# NyanTimer-v7.net
KiCad netlist of a schematic drawn in EAGLE
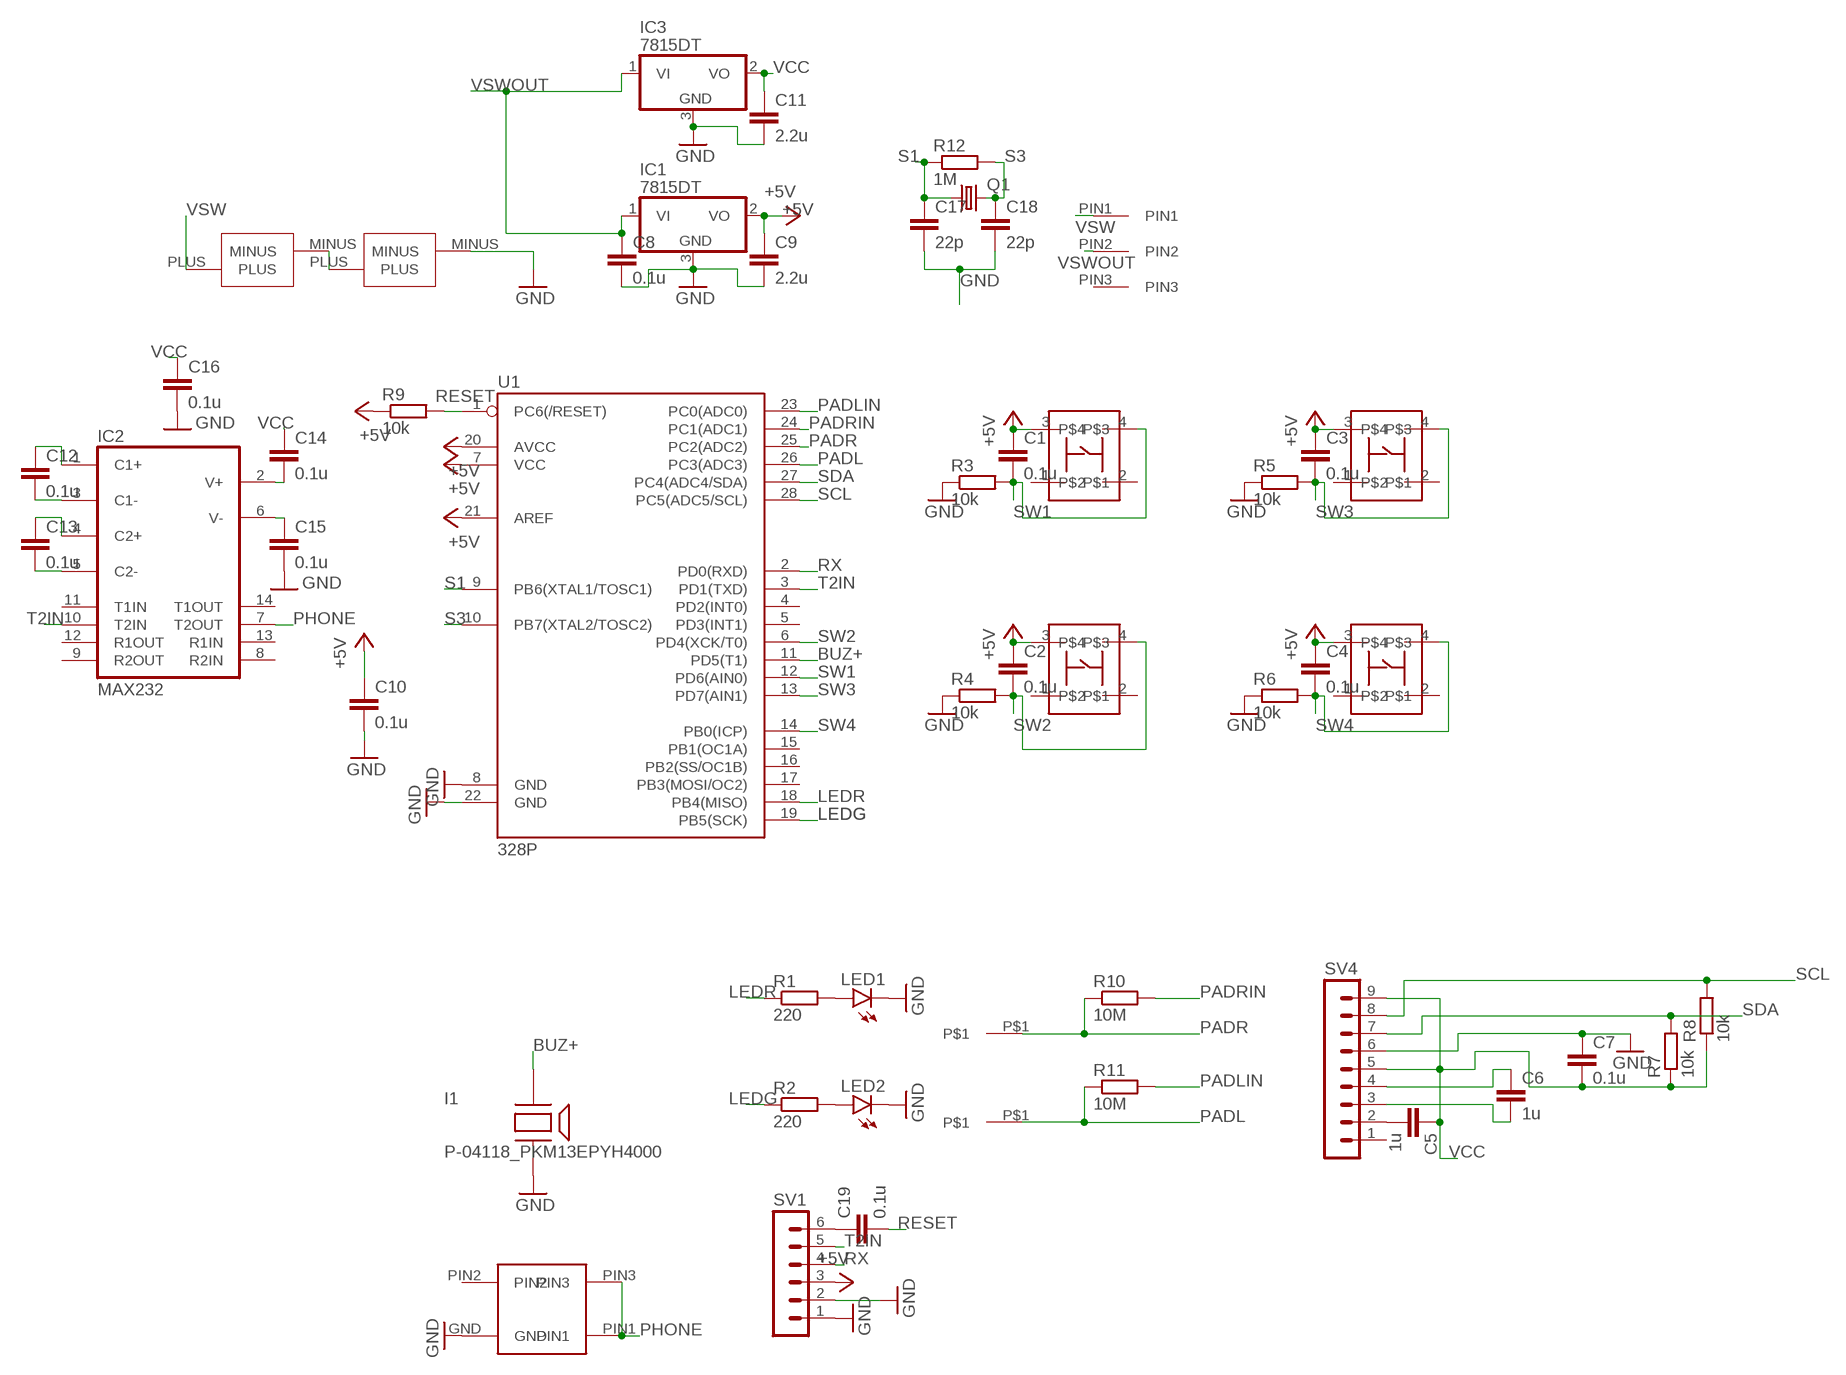
[diagram p0: schematic, sheet 1]

(export (version "E")
  (design (tool "Eeschema 10.0.6"))
  (components
    (comp (ref "BT1")
      (value "AKIZUKI_CR2032")
      (footprint "eagle-import:AKIZUKI_CR2032")
      (libsource (lib "eagle-import") (part "AKIZUKI_CR2032"))
    )
    (comp (ref "BT2")
      (value "AKIZUKI_CR2032")
      (footprint "eagle-import:AKIZUKI_CR2032")
      (libsource (lib "eagle-import") (part "AKIZUKI_CR2032"))
    )
    (comp (ref "C1")
      (value "0.1u")
      (footprint "eagle-import:C025-024X044")
      (libsource (lib "eagle-import") (part "C-EU025-024X044"))
    )
    (comp (ref "C2")
      (value "0.1u")
      (footprint "eagle-import:C025-024X044")
      (libsource (lib "eagle-import") (part "C-EU025-024X044"))
    )
    (comp (ref "C3")
      (value "0.1u")
      (footprint "eagle-import:C025-024X044")
      (libsource (lib "eagle-import") (part "C-EU025-024X044"))
    )
    (comp (ref "C4")
      (value "0.1u")
      (footprint "eagle-import:C025-024X044")
      (libsource (lib "eagle-import") (part "C-EU025-024X044"))
    )
    (comp (ref "C5")
      (value "1u")
      (footprint "eagle-import:C025-024X044")
      (libsource (lib "eagle-import") (part "C-EU025-024X044"))
    )
    (comp (ref "C6")
      (value "1u")
      (footprint "eagle-import:C025-024X044")
      (libsource (lib "eagle-import") (part "C-EU025-024X044"))
    )
    (comp (ref "C7")
      (value "0.1u")
      (footprint "eagle-import:C025-024X044")
      (libsource (lib "eagle-import") (part "C-EU025-024X044"))
    )
    (comp (ref "C8")
      (value "0.1u")
      (footprint "eagle-import:C025-024X044")
      (libsource (lib "eagle-import") (part "C-EU025-024X044"))
    )
    (comp (ref "C9")
      (value "2.2u")
      (footprint "eagle-import:C025-024X044")
      (libsource (lib "eagle-import") (part "C-EU025-024X044"))
    )
    (comp (ref "C10")
      (value "0.1u")
      (footprint "eagle-import:C025-024X044")
      (libsource (lib "eagle-import") (part "C-EU025-024X044"))
    )
    (comp (ref "C11")
      (value "2.2u")
      (footprint "eagle-import:C025-024X044")
      (libsource (lib "eagle-import") (part "C-EU025-024X044"))
    )
    (comp (ref "C12")
      (value "0.1u")
      (footprint "eagle-import:C025-024X044")
      (libsource (lib "eagle-import") (part "C-EU025-024X044"))
    )
    (comp (ref "C13")
      (value "0.1u")
      (footprint "eagle-import:C025-024X044")
      (libsource (lib "eagle-import") (part "C-EU025-024X044"))
    )
    (comp (ref "C14")
      (value "0.1u")
      (footprint "eagle-import:C025-024X044")
      (libsource (lib "eagle-import") (part "C-EU025-024X044"))
    )
    (comp (ref "C15")
      (value "0.1u")
      (footprint "eagle-import:C025-024X044")
      (libsource (lib "eagle-import") (part "C-EU025-024X044"))
    )
    (comp (ref "C16")
      (value "0.1u")
      (footprint "eagle-import:C025-024X044")
      (libsource (lib "eagle-import") (part "C-EU025-024X044"))
    )
    (comp (ref "C17")
      (value "22p")
      (footprint "eagle-import:C025-024X044")
      (libsource (lib "eagle-import") (part "C-EU025-024X044"))
    )
    (comp (ref "C18")
      (value "22p")
      (footprint "eagle-import:C025-024X044")
      (libsource (lib "eagle-import") (part "C-EU025-024X044"))
    )
    (comp (ref "C19")
      (value "0.1u")
      (footprint "eagle-import:C025-024X044")
      (libsource (lib "eagle-import") (part "C-EU025-024X044"))
    )
    (comp (ref "CONNECTOR1")
      (value "TACT_SWITCH")
      (footprint "eagle-import:TACT_SWITCH")
      (libsource (lib "eagle-import") (part "TACT_SWITCH"))
    )
    (comp (ref "CONNECTOR2")
      (value "TACT_SWITCH")
      (footprint "eagle-import:TACT_SWITCH")
      (libsource (lib "eagle-import") (part "TACT_SWITCH"))
    )
    (comp (ref "CONNECTOR3")
      (value "TACT_SWITCH")
      (footprint "eagle-import:TACT_SWITCH")
      (libsource (lib "eagle-import") (part "TACT_SWITCH"))
    )
    (comp (ref "CONNECTOR4")
      (value "TACT_SWITCH")
      (footprint "eagle-import:TACT_SWITCH")
      (libsource (lib "eagle-import") (part "TACT_SWITCH"))
    )
    (comp (ref "I1")
      (value "P-04118_PKM13EPYH4000")
      (footprint "eagle-import:PKM13EPYH4000")
      (libsource (lib "eagle-import") (part "P-04118_PKM13EPYH4000"))
    )
    (comp (ref "IC1")
      (value "7815DT")
      (footprint "eagle-import:TO252")
      (libsource (lib "eagle-import") (part "78DT15"))
    )
    (comp (ref "IC2")
      (value "MAX232")
      (footprint "eagle-import:DIL16")
      (fields (field (name "MF") "MAXIM") (field (name "MPN") "MAX232ACPE+"))
      (libsource (lib "eagle-import") (part "MAX232"))
    )
    (comp (ref "IC3")
      (value "7815DT")
      (footprint "eagle-import:TO252")
      (libsource (lib "eagle-import") (part "78DT15"))
    )
    (comp (ref "LED1")
      (value "LED3MM")
      (footprint "eagle-import:LED3MM")
      (libsource (lib "eagle-import") (part "LED3MM"))
    )
    (comp (ref "LED2")
      (value "LED3MM")
      (footprint "eagle-import:LED3MM")
      (libsource (lib "eagle-import") (part "LED3MM"))
    )
    (comp (ref "PHN1")
      (value "PHONE")
      (footprint "eagle-import:PHONE")
      (libsource (lib "eagle-import") (part "PHONE"))
    )
    (comp (ref "PIN1")
      (value "1PINHEAD")
      (footprint "eagle-import:1PINHEAD")
      (libsource (lib "eagle-import") (part "1PINHEAD"))
    )
    (comp (ref "PIN2")
      (value "1PINHEAD")
      (footprint "eagle-import:1PINHEAD")
      (libsource (lib "eagle-import") (part "1PINHEAD"))
    )
    (comp (ref "Q1")
      (value "CRYSTALHC49S")
      (footprint "eagle-import:HC49_S")
      (libsource (lib "eagle-import") (part "CRYSTALHC49S"))
    )
    (comp (ref "R1")
      (value "220")
      (footprint "eagle-import:0207_10")
      (libsource (lib "eagle-import") (part "R-EU_0207/10"))
    )
    (comp (ref "R2")
      (value "220")
      (footprint "eagle-import:0207_10")
      (libsource (lib "eagle-import") (part "R-EU_0207/10"))
    )
    (comp (ref "R3")
      (value "10k")
      (footprint "eagle-import:0207_10")
      (libsource (lib "eagle-import") (part "R-EU_0207/10"))
    )
    (comp (ref "R4")
      (value "10k")
      (footprint "eagle-import:0207_10")
      (libsource (lib "eagle-import") (part "R-EU_0207/10"))
    )
    (comp (ref "R5")
      (value "10k")
      (footprint "eagle-import:0207_10")
      (libsource (lib "eagle-import") (part "R-EU_0207/10"))
    )
    (comp (ref "R6")
      (value "10k")
      (footprint "eagle-import:0207_10")
      (libsource (lib "eagle-import") (part "R-EU_0207/10"))
    )
    (comp (ref "R7")
      (value "10k")
      (footprint "eagle-import:0207_10")
      (libsource (lib "eagle-import") (part "R-EU_0207/10"))
    )
    (comp (ref "R8")
      (value "10k")
      (footprint "eagle-import:0207_10")
      (libsource (lib "eagle-import") (part "R-EU_0207/10"))
    )
    (comp (ref "R9")
      (value "10k")
      (footprint "eagle-import:0207_10")
      (libsource (lib "eagle-import") (part "R-EU_0207/10"))
    )
    (comp (ref "R10")
      (value "10M")
      (footprint "eagle-import:0207_10")
      (libsource (lib "eagle-import") (part "R-EU_0207/10"))
    )
    (comp (ref "R11")
      (value "10M")
      (footprint "eagle-import:0207_10")
      (libsource (lib "eagle-import") (part "R-EU_0207/10"))
    )
    (comp (ref "R12")
      (value "1M")
      (footprint "eagle-import:0207_10")
      (libsource (lib "eagle-import") (part "R-EU_0207/10"))
    )
    (comp (ref "SV1")
      (value "MA06-1")
      (footprint "eagle-import:MA06-1")
      (libsource (lib "eagle-import") (part "MA06-1"))
    )
    (comp (ref "SV4")
      (value "MA09-1")
      (footprint "eagle-import:MA09-1")
      (libsource (lib "eagle-import") (part "MA09-1"))
    )
    (comp (ref "SW1")
      (value "AKIZUKI_SWITCH")
      (footprint "eagle-import:AKIZUKI_SWITCH")
      (libsource (lib "eagle-import") (part "AKIZUKI_SWITCH"))
    )
    (comp (ref "U1")
      (value "328P")
      (footprint "eagle-import:DIP28")
      (libsource (lib "eagle-import") (part "ATMEGA328P_PDIP"))
    )
  )
  (nets
    (net (code "1") (name "+5V") (class "Default")
      (node (ref "C1") (pin "1") (pinfunction "1_1") (pintype "passive"))
      (node (ref "C10") (pin "1") (pinfunction "1_1") (pintype "passive"))
      (node (ref "C2") (pin "1") (pinfunction "1_1") (pintype "passive"))
      (node (ref "C3") (pin "1") (pinfunction "1_1") (pintype "passive"))
      (node (ref "C4") (pin "1") (pinfunction "1_1") (pintype "passive"))
      (node (ref "C9") (pin "1") (pinfunction "1_1") (pintype "passive"))
      (node (ref "CONNECTOR1") (pin "3") (pinfunction "P$3_3") (pintype "bidirectional"))
      (node (ref "CONNECTOR2") (pin "3") (pinfunction "P$3_3") (pintype "bidirectional"))
      (node (ref "CONNECTOR3") (pin "3") (pinfunction "P$3_3") (pintype "bidirectional"))
      (node (ref "CONNECTOR4") (pin "3") (pinfunction "P$3_3") (pintype "bidirectional"))
      (node (ref "IC1") (pin "2") (pinfunction "VO_2") (pintype "passive"))
      (node (ref "R9") (pin "1") (pinfunction "1_1") (pintype "passive"))
      (node (ref "SV1") (pin "3") (pinfunction "3_3") (pintype "passive"))
      (node (ref "U1") (pin "20") (pinfunction "AVCC_20") (pintype "bidirectional"))
      (node (ref "U1") (pin "21") (pinfunction "AREF_21") (pintype "bidirectional"))
      (node (ref "U1") (pin "7") (pinfunction "VCC_7") (pintype "bidirectional"))
    )
    (net (code "2") (name "/BUZ+") (class "Default")
      (node (ref "I1") (pin "1") (pinfunction "1_1") (pintype "bidirectional"))
      (node (ref "U1") (pin "11") (pinfunction "PD5(T1)_11") (pintype "bidirectional"))
    )
    (net (code "3") (name "/LEDG") (class "Default")
      (node (ref "R2") (pin "1") (pinfunction "1_1") (pintype "passive"))
      (node (ref "U1") (pin "19") (pinfunction "PB5(SCK)_19") (pintype "bidirectional"))
    )
    (net (code "4") (name "/LEDR") (class "Default")
      (node (ref "R1") (pin "1") (pinfunction "1_1") (pintype "passive"))
      (node (ref "U1") (pin "18") (pinfunction "PB4(MISO)_18") (pintype "bidirectional"))
    )
    (net (code "5") (name "/PADL") (class "Default")
      (node (ref "PIN1") (pin "P$1") (pinfunction "P$1_P$1") (pintype "bidirectional"))
      (node (ref "R11") (pin "1") (pinfunction "1_1") (pintype "passive"))
      (node (ref "U1") (pin "26") (pinfunction "PC3(ADC3)_26") (pintype "bidirectional"))
    )
    (net (code "6") (name "/PADLIN") (class "Default")
      (node (ref "R11") (pin "2") (pinfunction "2_2") (pintype "passive"))
      (node (ref "U1") (pin "23") (pinfunction "PC0(ADC0)_23") (pintype "bidirectional"))
    )
    (net (code "7") (name "/PADR") (class "Default")
      (node (ref "PIN2") (pin "P$1") (pinfunction "P$1_P$1") (pintype "bidirectional"))
      (node (ref "R10") (pin "1") (pinfunction "1_1") (pintype "passive"))
      (node (ref "U1") (pin "25") (pinfunction "PC2(ADC2)_25") (pintype "bidirectional"))
    )
    (net (code "8") (name "/PADRIN") (class "Default")
      (node (ref "R10") (pin "2") (pinfunction "2_2") (pintype "passive"))
      (node (ref "U1") (pin "24") (pinfunction "PC1(ADC1)_24") (pintype "bidirectional"))
    )
    (net (code "9") (name "/PHONE") (class "Default")
      (node (ref "IC2") (pin "7") (pinfunction "T2OUT_7") (pintype "output"))
      (node (ref "PHN1") (pin "PIN1") (pinfunction "PIN1_PIN1") (pintype "bidirectional"))
      (node (ref "PHN1") (pin "PIN3") (pinfunction "PIN3_PIN3") (pintype "bidirectional"))
    )
    (net (code "10") (name "/RESET") (class "Default")
      (node (ref "C19") (pin "2") (pinfunction "2_2") (pintype "passive"))
      (node (ref "R9") (pin "2") (pinfunction "2_2") (pintype "passive"))
      (node (ref "U1") (pin "1") (pinfunction "PC6(/RESET)_1") (pintype "bidirectional"))
    )
    (net (code "11") (name "/RX") (class "Default")
      (node (ref "SV1") (pin "4") (pinfunction "4_4") (pintype "passive"))
      (node (ref "U1") (pin "2") (pinfunction "PD0(RXD)_2") (pintype "bidirectional"))
    )
    (net (code "12") (name "/S1") (class "Default")
      (node (ref "C17") (pin "1") (pinfunction "1_1") (pintype "passive"))
      (node (ref "Q1") (pin "1") (pinfunction "1_1") (pintype "passive"))
      (node (ref "R12") (pin "1") (pinfunction "1_1") (pintype "passive"))
      (node (ref "U1") (pin "9") (pinfunction "PB6(XTAL1/TOSC1)_9") (pintype "bidirectional"))
    )
    (net (code "13") (name "/S3") (class "Default")
      (node (ref "C18") (pin "1") (pinfunction "1_1") (pintype "passive"))
      (node (ref "Q1") (pin "2") (pinfunction "2_2") (pintype "passive"))
      (node (ref "R12") (pin "2") (pinfunction "2_2") (pintype "passive"))
      (node (ref "U1") (pin "10") (pinfunction "PB7(XTAL2/TOSC2)_10") (pintype "bidirectional"))
    )
    (net (code "14") (name "/SCL") (class "Default")
      (node (ref "R8") (pin "2") (pinfunction "2_2") (pintype "passive"))
      (node (ref "SV4") (pin "8") (pinfunction "8_8") (pintype "passive"))
      (node (ref "U1") (pin "28") (pinfunction "PC5(ADC5/SCL)_28") (pintype "bidirectional"))
    )
    (net (code "15") (name "/SDA") (class "Default")
      (node (ref "R7") (pin "2") (pinfunction "2_2") (pintype "passive"))
      (node (ref "SV4") (pin "7") (pinfunction "7_7") (pintype "passive"))
      (node (ref "U1") (pin "27") (pinfunction "PC4(ADC4/SDA)_27") (pintype "bidirectional"))
    )
    (net (code "16") (name "/SW1") (class "Default")
      (node (ref "C1") (pin "2") (pinfunction "2_2") (pintype "passive"))
      (node (ref "CONNECTOR1") (pin "4") (pinfunction "P$4_4") (pintype "bidirectional"))
      (node (ref "R3") (pin "2") (pinfunction "2_2") (pintype "passive"))
      (node (ref "U1") (pin "12") (pinfunction "PD6(AIN0)_12") (pintype "bidirectional"))
    )
    (net (code "17") (name "/SW2") (class "Default")
      (node (ref "C2") (pin "2") (pinfunction "2_2") (pintype "passive"))
      (node (ref "CONNECTOR2") (pin "4") (pinfunction "P$4_4") (pintype "bidirectional"))
      (node (ref "R4") (pin "2") (pinfunction "2_2") (pintype "passive"))
      (node (ref "U1") (pin "6") (pinfunction "PD4(XCK/T0)_6") (pintype "bidirectional"))
    )
    (net (code "18") (name "/SW3") (class "Default")
      (node (ref "C3") (pin "2") (pinfunction "2_2") (pintype "passive"))
      (node (ref "CONNECTOR3") (pin "4") (pinfunction "P$4_4") (pintype "bidirectional"))
      (node (ref "R5") (pin "2") (pinfunction "2_2") (pintype "passive"))
      (node (ref "U1") (pin "13") (pinfunction "PD7(AIN1)_13") (pintype "bidirectional"))
    )
    (net (code "19") (name "/SW4") (class "Default")
      (node (ref "C4") (pin "2") (pinfunction "2_2") (pintype "passive"))
      (node (ref "CONNECTOR4") (pin "4") (pinfunction "P$4_4") (pintype "bidirectional"))
      (node (ref "R6") (pin "2") (pinfunction "2_2") (pintype "passive"))
      (node (ref "U1") (pin "14") (pinfunction "PB0(ICP)_14") (pintype "bidirectional"))
    )
    (net (code "20") (name "/T2IN") (class "Default")
      (node (ref "IC2") (pin "10") (pinfunction "T2IN_10") (pintype "input"))
      (node (ref "SV1") (pin "5") (pinfunction "5_5") (pintype "passive"))
      (node (ref "U1") (pin "3") (pinfunction "PD1(TXD)_3") (pintype "bidirectional"))
    )
    (net (code "21") (name "/VCC") (class "Default")
      (node (ref "C11") (pin "1") (pinfunction "1_1") (pintype "passive"))
      (node (ref "C14") (pin "1") (pinfunction "1_1") (pintype "passive"))
      (node (ref "C16") (pin "1") (pinfunction "1_1") (pintype "passive"))
      (node (ref "C5") (pin "1") (pinfunction "1_1") (pintype "passive"))
      (node (ref "C7") (pin "2") (pinfunction "2_2") (pintype "passive"))
      (node (ref "IC3") (pin "2") (pinfunction "VO_2") (pintype "passive"))
      (node (ref "R7") (pin "1") (pinfunction "1_1") (pintype "passive"))
      (node (ref "R8") (pin "1") (pinfunction "1_1") (pintype "passive"))
      (node (ref "SV4") (pin "5") (pinfunction "5_5") (pintype "passive"))
      (node (ref "SV4") (pin "9") (pinfunction "9_9") (pintype "passive"))
    )
    (net (code "22") (name "/VSW") (class "Default")
      (node (ref "BT1") (pin "PLUS") (pinfunction "PLUS_PLUS") (pintype "bidirectional"))
      (node (ref "SW1") (pin "PIN1") (pinfunction "PIN1_PIN1") (pintype "bidirectional"))
    )
    (net (code "23") (name "/VSWOUT") (class "Default")
      (node (ref "C8") (pin "1") (pinfunction "1_1") (pintype "passive"))
      (node (ref "IC1") (pin "1") (pinfunction "VI_1") (pintype "input"))
      (node (ref "IC3") (pin "1") (pinfunction "VI_1") (pintype "input"))
      (node (ref "SW1") (pin "PIN2") (pinfunction "PIN2_PIN2") (pintype "bidirectional"))
    )
    (net (code "24") (name "GND") (class "Default")
      (node (ref "BT2") (pin "MINUS") (pinfunction "MINUS_MINUS") (pintype "bidirectional"))
      (node (ref "C10") (pin "2") (pinfunction "2_2") (pintype "passive"))
      (node (ref "C11") (pin "2") (pinfunction "2_2") (pintype "passive"))
      (node (ref "C15") (pin "2") (pinfunction "2_2") (pintype "passive"))
      (node (ref "C16") (pin "2") (pinfunction "2_2") (pintype "passive"))
      (node (ref "C17") (pin "2") (pinfunction "2_2") (pintype "passive"))
      (node (ref "C18") (pin "2") (pinfunction "2_2") (pintype "passive"))
      (node (ref "C7") (pin "1") (pinfunction "1_1") (pintype "passive"))
      (node (ref "C8") (pin "2") (pinfunction "2_2") (pintype "passive"))
      (node (ref "C9") (pin "2") (pinfunction "2_2") (pintype "passive"))
      (node (ref "I1") (pin "2") (pinfunction "2_2") (pintype "bidirectional"))
      (node (ref "IC1") (pin "3") (pinfunction "GND_3") (pintype "passive"))
      (node (ref "IC3") (pin "3") (pinfunction "GND_3") (pintype "passive"))
      (node (ref "LED1") (pin "K") (pinfunction "C_K") (pintype "passive"))
      (node (ref "LED2") (pin "K") (pinfunction "C_K") (pintype "passive"))
      (node (ref "PHN1") (pin "GND") (pinfunction "GND_GND") (pintype "bidirectional"))
      (node (ref "R3") (pin "1") (pinfunction "1_1") (pintype "passive"))
      (node (ref "R4") (pin "1") (pinfunction "1_1") (pintype "passive"))
      (node (ref "R5") (pin "1") (pinfunction "1_1") (pintype "passive"))
      (node (ref "R6") (pin "1") (pinfunction "1_1") (pintype "passive"))
      (node (ref "SV1") (pin "1") (pinfunction "1_1") (pintype "passive"))
      (node (ref "SV1") (pin "2") (pinfunction "2_2") (pintype "passive"))
      (node (ref "SV4") (pin "6") (pinfunction "6_6") (pintype "passive"))
      (node (ref "U1") (pin "22") (pinfunction "GND_22") (pintype "bidirectional"))
      (node (ref "U1") (pin "8") (pinfunction "GND_8") (pintype "bidirectional"))
    )
    (net (code "25") (name "Net-(BT1-PadMINUS)") (class "Default")
      (node (ref "BT1") (pin "MINUS") (pinfunction "MINUS_MINUS") (pintype "bidirectional"))
      (node (ref "BT2") (pin "PLUS") (pinfunction "PLUS_PLUS") (pintype "bidirectional"))
    )
    (net (code "26") (name "Net-(C5-Pad2)") (class "Default")
      (node (ref "C5") (pin "2") (pinfunction "2_2") (pintype "passive"))
      (node (ref "SV4") (pin "2") (pinfunction "2_2") (pintype "passive"))
    )
    (net (code "27") (name "Net-(C6-Pad1)") (class "Default")
      (node (ref "C6") (pin "1") (pinfunction "1_1") (pintype "passive"))
      (node (ref "SV4") (pin "4") (pinfunction "4_4") (pintype "passive"))
    )
    (net (code "28") (name "Net-(C6-Pad2)") (class "Default")
      (node (ref "C6") (pin "2") (pinfunction "2_2") (pintype "passive"))
      (node (ref "SV4") (pin "3") (pinfunction "3_3") (pintype "passive"))
    )
    (net (code "29") (name "Net-(C19-Pad1)") (class "Default")
      (node (ref "C19") (pin "1") (pinfunction "1_1") (pintype "passive"))
      (node (ref "SV1") (pin "6") (pinfunction "6_6") (pintype "passive"))
    )
    (net (code "30") (name "Net-(IC2A-C1+)") (class "Default")
      (node (ref "C12") (pin "1") (pinfunction "1_1") (pintype "passive"))
      (node (ref "IC2") (pin "1") (pinfunction "C1+_1") (pintype "bidirectional"))
    )
    (net (code "31") (name "Net-(IC2A-C1-)") (class "Default")
      (node (ref "C12") (pin "2") (pinfunction "2_2") (pintype "passive"))
      (node (ref "IC2") (pin "3") (pinfunction "C1-_3") (pintype "bidirectional"))
    )
    (net (code "32") (name "Net-(IC2A-C2+)") (class "Default")
      (node (ref "C13") (pin "1") (pinfunction "1_1") (pintype "passive"))
      (node (ref "IC2") (pin "4") (pinfunction "C2+_4") (pintype "bidirectional"))
    )
    (net (code "33") (name "Net-(IC2A-C2-)") (class "Default")
      (node (ref "C13") (pin "2") (pinfunction "2_2") (pintype "passive"))
      (node (ref "IC2") (pin "5") (pinfunction "C2-_5") (pintype "bidirectional"))
    )
    (net (code "34") (name "Net-(IC2A-V+)") (class "Default")
      (node (ref "C14") (pin "2") (pinfunction "2_2") (pintype "passive"))
      (node (ref "IC2") (pin "2") (pinfunction "V+_2") (pintype "bidirectional"))
    )
    (net (code "35") (name "Net-(IC2A-V-)") (class "Default")
      (node (ref "C15") (pin "1") (pinfunction "1_1") (pintype "passive"))
      (node (ref "IC2") (pin "6") (pinfunction "V-_6") (pintype "bidirectional"))
    )
    (net (code "36") (name "Net-(LED1-PadA)") (class "Default")
      (node (ref "LED1") (pin "A") (pinfunction "A_A") (pintype "passive"))
      (node (ref "R1") (pin "2") (pinfunction "2_2") (pintype "passive"))
    )
    (net (code "37") (name "Net-(LED2-PadA)") (class "Default")
      (node (ref "LED2") (pin "A") (pinfunction "A_A") (pintype "passive"))
      (node (ref "R2") (pin "2") (pinfunction "2_2") (pintype "passive"))
    )
    (net (code "38") (name "unconnected-(CONNECTOR1-P$1-Pad1)") (class "Default")
      (node (ref "CONNECTOR1") (pin "1") (pinfunction "P$1_1") (pintype "bidirectional"))
    )
    (net (code "39") (name "unconnected-(CONNECTOR1-P$2-Pad2)") (class "Default")
      (node (ref "CONNECTOR1") (pin "2") (pinfunction "P$2_2") (pintype "bidirectional"))
    )
    (net (code "40") (name "unconnected-(CONNECTOR2-P$1-Pad1)") (class "Default")
      (node (ref "CONNECTOR2") (pin "1") (pinfunction "P$1_1") (pintype "bidirectional"))
    )
    (net (code "41") (name "unconnected-(CONNECTOR2-P$2-Pad2)") (class "Default")
      (node (ref "CONNECTOR2") (pin "2") (pinfunction "P$2_2") (pintype "bidirectional"))
    )
    (net (code "42") (name "unconnected-(CONNECTOR3-P$1-Pad1)") (class "Default")
      (node (ref "CONNECTOR3") (pin "1") (pinfunction "P$1_1") (pintype "bidirectional"))
    )
    (net (code "43") (name "unconnected-(CONNECTOR3-P$2-Pad2)") (class "Default")
      (node (ref "CONNECTOR3") (pin "2") (pinfunction "P$2_2") (pintype "bidirectional"))
    )
    (net (code "44") (name "unconnected-(CONNECTOR4-P$1-Pad1)") (class "Default")
      (node (ref "CONNECTOR4") (pin "1") (pinfunction "P$1_1") (pintype "bidirectional"))
    )
    (net (code "45") (name "unconnected-(CONNECTOR4-P$2-Pad2)") (class "Default")
      (node (ref "CONNECTOR4") (pin "2") (pinfunction "P$2_2") (pintype "bidirectional"))
    )
    (net (code "46") (name "unconnected-(IC2A-R1IN-Pad13)") (class "Default")
      (node (ref "IC2") (pin "13") (pinfunction "R1IN_13") (pintype "input"))
    )
    (net (code "47") (name "unconnected-(IC2A-R1OUT-Pad12)") (class "Default")
      (node (ref "IC2") (pin "12") (pinfunction "R1OUT_12") (pintype "output"))
    )
    (net (code "48") (name "unconnected-(IC2A-R2IN-Pad8)") (class "Default")
      (node (ref "IC2") (pin "8") (pinfunction "R2IN_8") (pintype "input"))
    )
    (net (code "49") (name "unconnected-(IC2A-R2OUT-Pad9)") (class "Default")
      (node (ref "IC2") (pin "9") (pinfunction "R2OUT_9") (pintype "output"))
    )
    (net (code "50") (name "unconnected-(IC2A-T1IN-Pad11)") (class "Default")
      (node (ref "IC2") (pin "11") (pinfunction "T1IN_11") (pintype "input"))
    )
    (net (code "51") (name "unconnected-(IC2A-T1OUT-Pad14)") (class "Default")
      (node (ref "IC2") (pin "14") (pinfunction "T1OUT_14") (pintype "output"))
    )
    (net (code "52") (name "unconnected-(PHN1-PadPIN2)") (class "Default")
      (node (ref "PHN1") (pin "PIN2") (pinfunction "PIN2_PIN2") (pintype "bidirectional"))
    )
    (net (code "53") (name "unconnected-(SV4-Pad1)") (class "Default")
      (node (ref "SV4") (pin "1") (pinfunction "1_1") (pintype "passive"))
    )
    (net (code "54") (name "unconnected-(SW1-PadPIN3)") (class "Default")
      (node (ref "SW1") (pin "PIN3") (pinfunction "PIN3_PIN3") (pintype "bidirectional"))
    )
    (net (code "55") (name "unconnected-(U1-PB1(OC1A)-Pad15)") (class "Default")
      (node (ref "U1") (pin "15") (pinfunction "PB1(OC1A)_15") (pintype "bidirectional"))
    )
    (net (code "56") (name "unconnected-(U1-PB2(SS{slash}OC1B)-Pad16)") (class "Default")
      (node (ref "U1") (pin "16") (pinfunction "PB2(SS/OC1B)_16") (pintype "bidirectional"))
    )
    (net (code "57") (name "unconnected-(U1-PB3(MOSI{slash}OC2)-Pad17)") (class "Default")
      (node (ref "U1") (pin "17") (pinfunction "PB3(MOSI/OC2)_17") (pintype "bidirectional"))
    )
    (net (code "58") (name "unconnected-(U1-PD2(INT0)-Pad4)") (class "Default")
      (node (ref "U1") (pin "4") (pinfunction "PD2(INT0)_4") (pintype "bidirectional"))
    )
    (net (code "59") (name "unconnected-(U1-PD3(INT1)-Pad5)") (class "Default")
      (node (ref "U1") (pin "5") (pinfunction "PD3(INT1)_5") (pintype "bidirectional"))
    )
  )
)
